# 03_UART_232.net
KiCad netlist of a schematic drawn in Altium Designer
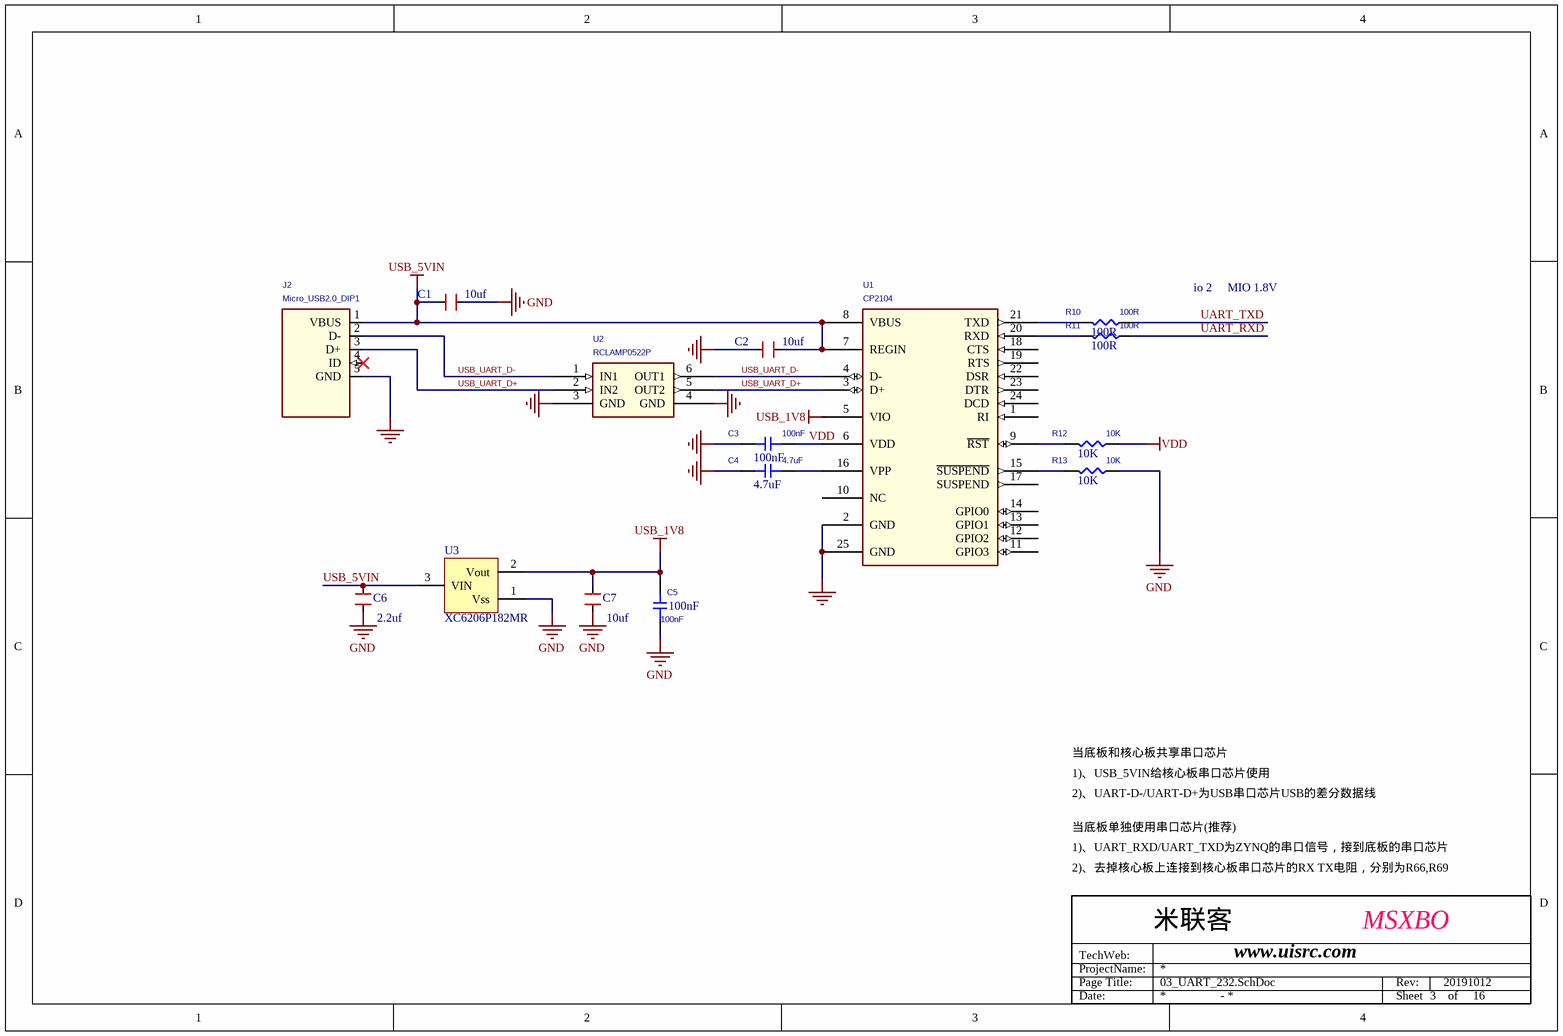
[diagram p0: 03_UART_232.SchDoc]

(export (version "E")
  (design (tool "Eeschema 10.0.6"))
  (components
    (comp (ref "C1")
      (value "10uf")
      (footprint "CAP0603")
      (description "Generic Capacitor")
      (libsource (lib "Digilent") (part "CAPACITOR"))
    )
    (comp (ref "C2")
      (value "10uf")
      (footprint "CAP0603")
      (description "Generic Capacitor")
      (libsource (lib "Digilent") (part "CAPACITOR"))
    )
    (comp (ref "C3")
      (value "100nF")
      (footprint "C0603")
      (fields (field (name "VOLTAGE") "CMAX") (field (name "ALTIUM_VALUE") "100nF"))
      (libsource (lib "*") (part "CAP1"))
    )
    (comp (ref "C4")
      (value "4.7uF")
      (footprint "C0603")
      (fields (field (name "VOLTAGE") "CMAX") (field (name "ALTIUM_VALUE") "4.7uF"))
      (libsource (lib "*") (part "CAP1"))
    )
    (comp (ref "C5")
      (value "100nF")
      (footprint "C0603")
      (fields (field (name "VOLTAGE") "CMAX") (field (name "ALTIUM_VALUE") "100nF"))
      (libsource (lib "*") (part "CAP1"))
    )
    (comp (ref "C6")
      (value "2.2uf")
      (footprint "CAP0603")
      (description "Generic Capacitor")
      (libsource (lib "Digilent") (part "CAPACITOR"))
    )
    (comp (ref "C7")
      (value "10uf")
      (footprint "CAP0603")
      (description "Generic Capacitor")
      (libsource (lib "Digilent") (part "CAPACITOR"))
    )
    (comp (ref "J2")
      (value "Micro_USB2.0_DIP1")
      (footprint "MicroUsb")
      (libsource (lib "*") (part "Micro_USB2_0.0_DIP1"))
    )
    (comp (ref "R10")
      (value "100R")
      (footprint "R0603")
      (fields
        (field (name "VOLTAGE") "RVMAX")
        (field (name "POWER") "RMAX")
        (field (name "ALTIUM_VALUE") "100R")
      )
      (libsource (lib "*") (part "RES1"))
    )
    (comp (ref "R11")
      (value "100R")
      (footprint "R0603")
      (fields
        (field (name "VOLTAGE") "RVMAX")
        (field (name "POWER") "RMAX")
        (field (name "ALTIUM_VALUE") "100R")
      )
      (libsource (lib "*") (part "RES1"))
    )
    (comp (ref "R12")
      (value "10K")
      (footprint "R0603")
      (fields
        (field (name "VOLTAGE") "RVMAX")
        (field (name "POWER") "RMAX")
        (field (name "ALTIUM_VALUE") "10K")
      )
      (libsource (lib "*") (part "RES1"))
    )
    (comp (ref "R13")
      (value "10K")
      (footprint "R0603")
      (fields
        (field (name "VOLTAGE") "RVMAX")
        (field (name "POWER") "RMAX")
        (field (name "ALTIUM_VALUE") "10K")
      )
      (libsource (lib "*") (part "RES1"))
    )
    (comp (ref "U1") (value "CP2104") (footprint "QFN24_50P4X4X1") (libsource (lib "*") (part "CP2104")))
    (comp (ref "U2")
      (value "RCLAMP0522P")
      (footprint "SLP1610P4_6")
      (libsource (lib "*") (part "RCLAMP0522P"))
    )
    (comp (ref "U3")
      (value "XC6206P182MR")
      (footprint "SOT23")
      (libsource (lib "MIZ7035_Fun") (part "XC6206P332MR"))
    )
  )
  (nets
    (net (code "1") (name "/UART_RXD") (class "Default")
      (node (ref "R11") (pin "2") (pinfunction "2_2") (pintype "passive"))
    )
    (net (code "2") (name "/UART_TXD") (class "Default")
      (node (ref "R10") (pin "2") (pinfunction "2_2") (pintype "passive"))
    )
    (net (code "3") (name "/USB_UART_D+") (class "Default")
      (node (ref "J2") (pin "3") (pinfunction "D+_3") (pintype "bidirectional"))
      (node (ref "U1") (pin "3") (pinfunction "D+_3") (pintype "bidirectional"))
      (node (ref "U2") (pin "2") (pinfunction "IN2_2") (pintype "input"))
      (node (ref "U2") (pin "5") (pinfunction "OUT2_5") (pintype "output"))
    )
    (net (code "4") (name "/USB_UART_D-") (class "Default")
      (node (ref "J2") (pin "2") (pinfunction "D-_2") (pintype "bidirectional"))
      (node (ref "U1") (pin "4") (pinfunction "D-_4") (pintype "bidirectional"))
      (node (ref "U2") (pin "1") (pinfunction "IN1_1") (pintype "input"))
      (node (ref "U2") (pin "6") (pinfunction "OUT1_6") (pintype "output"))
    )
    (net (code "5") (name "GND") (class "Default")
      (node (ref "C1") (pin "1") (pinfunction "1_1") (pintype "passive"))
      (node (ref "C2") (pin "2") (pinfunction "2_2") (pintype "passive"))
      (node (ref "C3") (pin "1") (pinfunction "1_1") (pintype "passive"))
      (node (ref "C4") (pin "1") (pinfunction "1_1") (pintype "passive"))
      (node (ref "C5") (pin "1") (pinfunction "1_1") (pintype "passive"))
      (node (ref "C6") (pin "1") (pinfunction "1_1") (pintype "passive"))
      (node (ref "C7") (pin "1") (pinfunction "1_1") (pintype "passive"))
      (node (ref "J2") (pin "5") (pinfunction "GND_5") (pintype "power_in"))
      (node (ref "R13") (pin "2") (pinfunction "2_2") (pintype "passive"))
      (node (ref "U1") (pin "2") (pinfunction "GND_2") (pintype "power_in"))
      (node (ref "U1") (pin "25") (pinfunction "GND_25") (pintype "power_in"))
      (node (ref "U2") (pin "3") (pinfunction "GND_3") (pintype "power_in"))
      (node (ref "U2") (pin "4") (pinfunction "GND_4") (pintype "power_in"))
      (node (ref "U3") (pin "1") (pinfunction "Vss_1") (pintype "passive"))
    )
    (net (code "6") (name "Net-(U1-RXD)") (class "Default")
      (node (ref "R11") (pin "1") (pinfunction "1_1") (pintype "passive"))
      (node (ref "U1") (pin "20") (pinfunction "RXD_20") (pintype "input"))
    )
    (net (code "7") (name "Net-(U1-TXD)") (class "Default")
      (node (ref "R10") (pin "1") (pinfunction "1_1") (pintype "passive"))
      (node (ref "U1") (pin "21") (pinfunction "TXD_21") (pintype "output"))
    )
    (net (code "8") (name "Net-(U1-VPP)") (class "Default")
      (node (ref "C4") (pin "2") (pinfunction "2_2") (pintype "passive"))
      (node (ref "U1") (pin "16") (pinfunction "VPP_16") (pintype "passive"))
    )
    (net (code "9") (name "Net-(U1-~{RST})") (class "Default")
      (node (ref "R12") (pin "1") (pinfunction "1_1") (pintype "passive"))
      (node (ref "U1") (pin "9") (pinfunction "~{RST}_9") (pintype "bidirectional"))
    )
    (net (code "10") (name "Net-(U1-~{SUSPEND})") (class "Default")
      (node (ref "R13") (pin "1") (pinfunction "1_1") (pintype "passive"))
      (node (ref "U1") (pin "15") (pinfunction "~{SUSPEND}_15") (pintype "output"))
    )
    (net (code "11") (name "USB_1V8") (class "Default")
      (node (ref "C5") (pin "2") (pinfunction "2_2") (pintype "passive"))
      (node (ref "C7") (pin "2") (pinfunction "2_2") (pintype "passive"))
      (node (ref "U1") (pin "5") (pinfunction "VIO_5") (pintype "power_in"))
      (node (ref "U3") (pin "2") (pinfunction "Vout_2") (pintype "passive"))
    )
    (net (code "12") (name "USB_5VIN") (class "Default")
      (node (ref "C1") (pin "2") (pinfunction "2_2") (pintype "passive"))
      (node (ref "C2") (pin "1") (pinfunction "1_1") (pintype "passive"))
      (node (ref "C6") (pin "2") (pinfunction "2_2") (pintype "passive"))
      (node (ref "J2") (pin "1") (pinfunction "VBUS_1") (pintype "power_in"))
      (node (ref "U1") (pin "7") (pinfunction "REGIN_7") (pintype "power_in"))
      (node (ref "U1") (pin "8") (pinfunction "VBUS_8") (pintype "power_in"))
      (node (ref "U3") (pin "3") (pinfunction "VIN_3") (pintype "passive"))
    )
    (net (code "13") (name "VDD") (class "Default")
      (node (ref "C3") (pin "2") (pinfunction "2_2") (pintype "passive"))
      (node (ref "R12") (pin "2") (pinfunction "2_2") (pintype "passive"))
      (node (ref "U1") (pin "6") (pinfunction "VDD_6") (pintype "power_in"))
    )
    (net (code "14") (name "unconnected-(J2-ID-Pad4)") (class "Default")
      (node (ref "J2") (pin "4") (pinfunction "ID_4") (pintype "input+no_connect"))
    )
    (net (code "15") (name "unconnected-(U1-CTS-Pad18)") (class "Default")
      (node (ref "U1") (pin "18") (pinfunction "CTS_18") (pintype "input"))
    )
    (net (code "16") (name "unconnected-(U1-DCD-Pad24)") (class "Default")
      (node (ref "U1") (pin "24") (pinfunction "DCD_24") (pintype "input"))
    )
    (net (code "17") (name "unconnected-(U1-DSR-Pad22)") (class "Default")
      (node (ref "U1") (pin "22") (pinfunction "DSR_22") (pintype "input"))
    )
    (net (code "18") (name "unconnected-(U1-DTR-Pad23)") (class "Default")
      (node (ref "U1") (pin "23") (pinfunction "DTR_23") (pintype "output"))
    )
    (net (code "19") (name "unconnected-(U1-GPIO0-Pad14)") (class "Default")
      (node (ref "U1") (pin "14") (pinfunction "GPIO0_14") (pintype "bidirectional"))
    )
    (net (code "20") (name "unconnected-(U1-GPIO1-Pad13)") (class "Default")
      (node (ref "U1") (pin "13") (pinfunction "GPIO1_13") (pintype "bidirectional"))
    )
    (net (code "21") (name "unconnected-(U1-GPIO2-Pad12)") (class "Default")
      (node (ref "U1") (pin "12") (pinfunction "GPIO2_12") (pintype "bidirectional"))
    )
    (net (code "22") (name "unconnected-(U1-GPIO3-Pad11)") (class "Default")
      (node (ref "U1") (pin "11") (pinfunction "GPIO3_11") (pintype "bidirectional"))
    )
    (net (code "23") (name "unconnected-(U1-NC-Pad10)") (class "Default")
      (node (ref "U1") (pin "10") (pinfunction "NC_10") (pintype "passive"))
    )
    (net (code "24") (name "unconnected-(U1-RI-Pad1)") (class "Default")
      (node (ref "U1") (pin "1") (pinfunction "RI_1") (pintype "input"))
    )
    (net (code "25") (name "unconnected-(U1-RTS-Pad19)") (class "Default")
      (node (ref "U1") (pin "19") (pinfunction "RTS_19") (pintype "output"))
    )
    (net (code "26") (name "unconnected-(U1-SUSPEND-Pad17)") (class "Default")
      (node (ref "U1") (pin "17") (pinfunction "SUSPEND_17") (pintype "output"))
    )
  )
)
